# SCH_RFID_FCMS_Pi_Shield_2022-05-20.net
KiCad netlist of a schematic drawn in EasyEDA
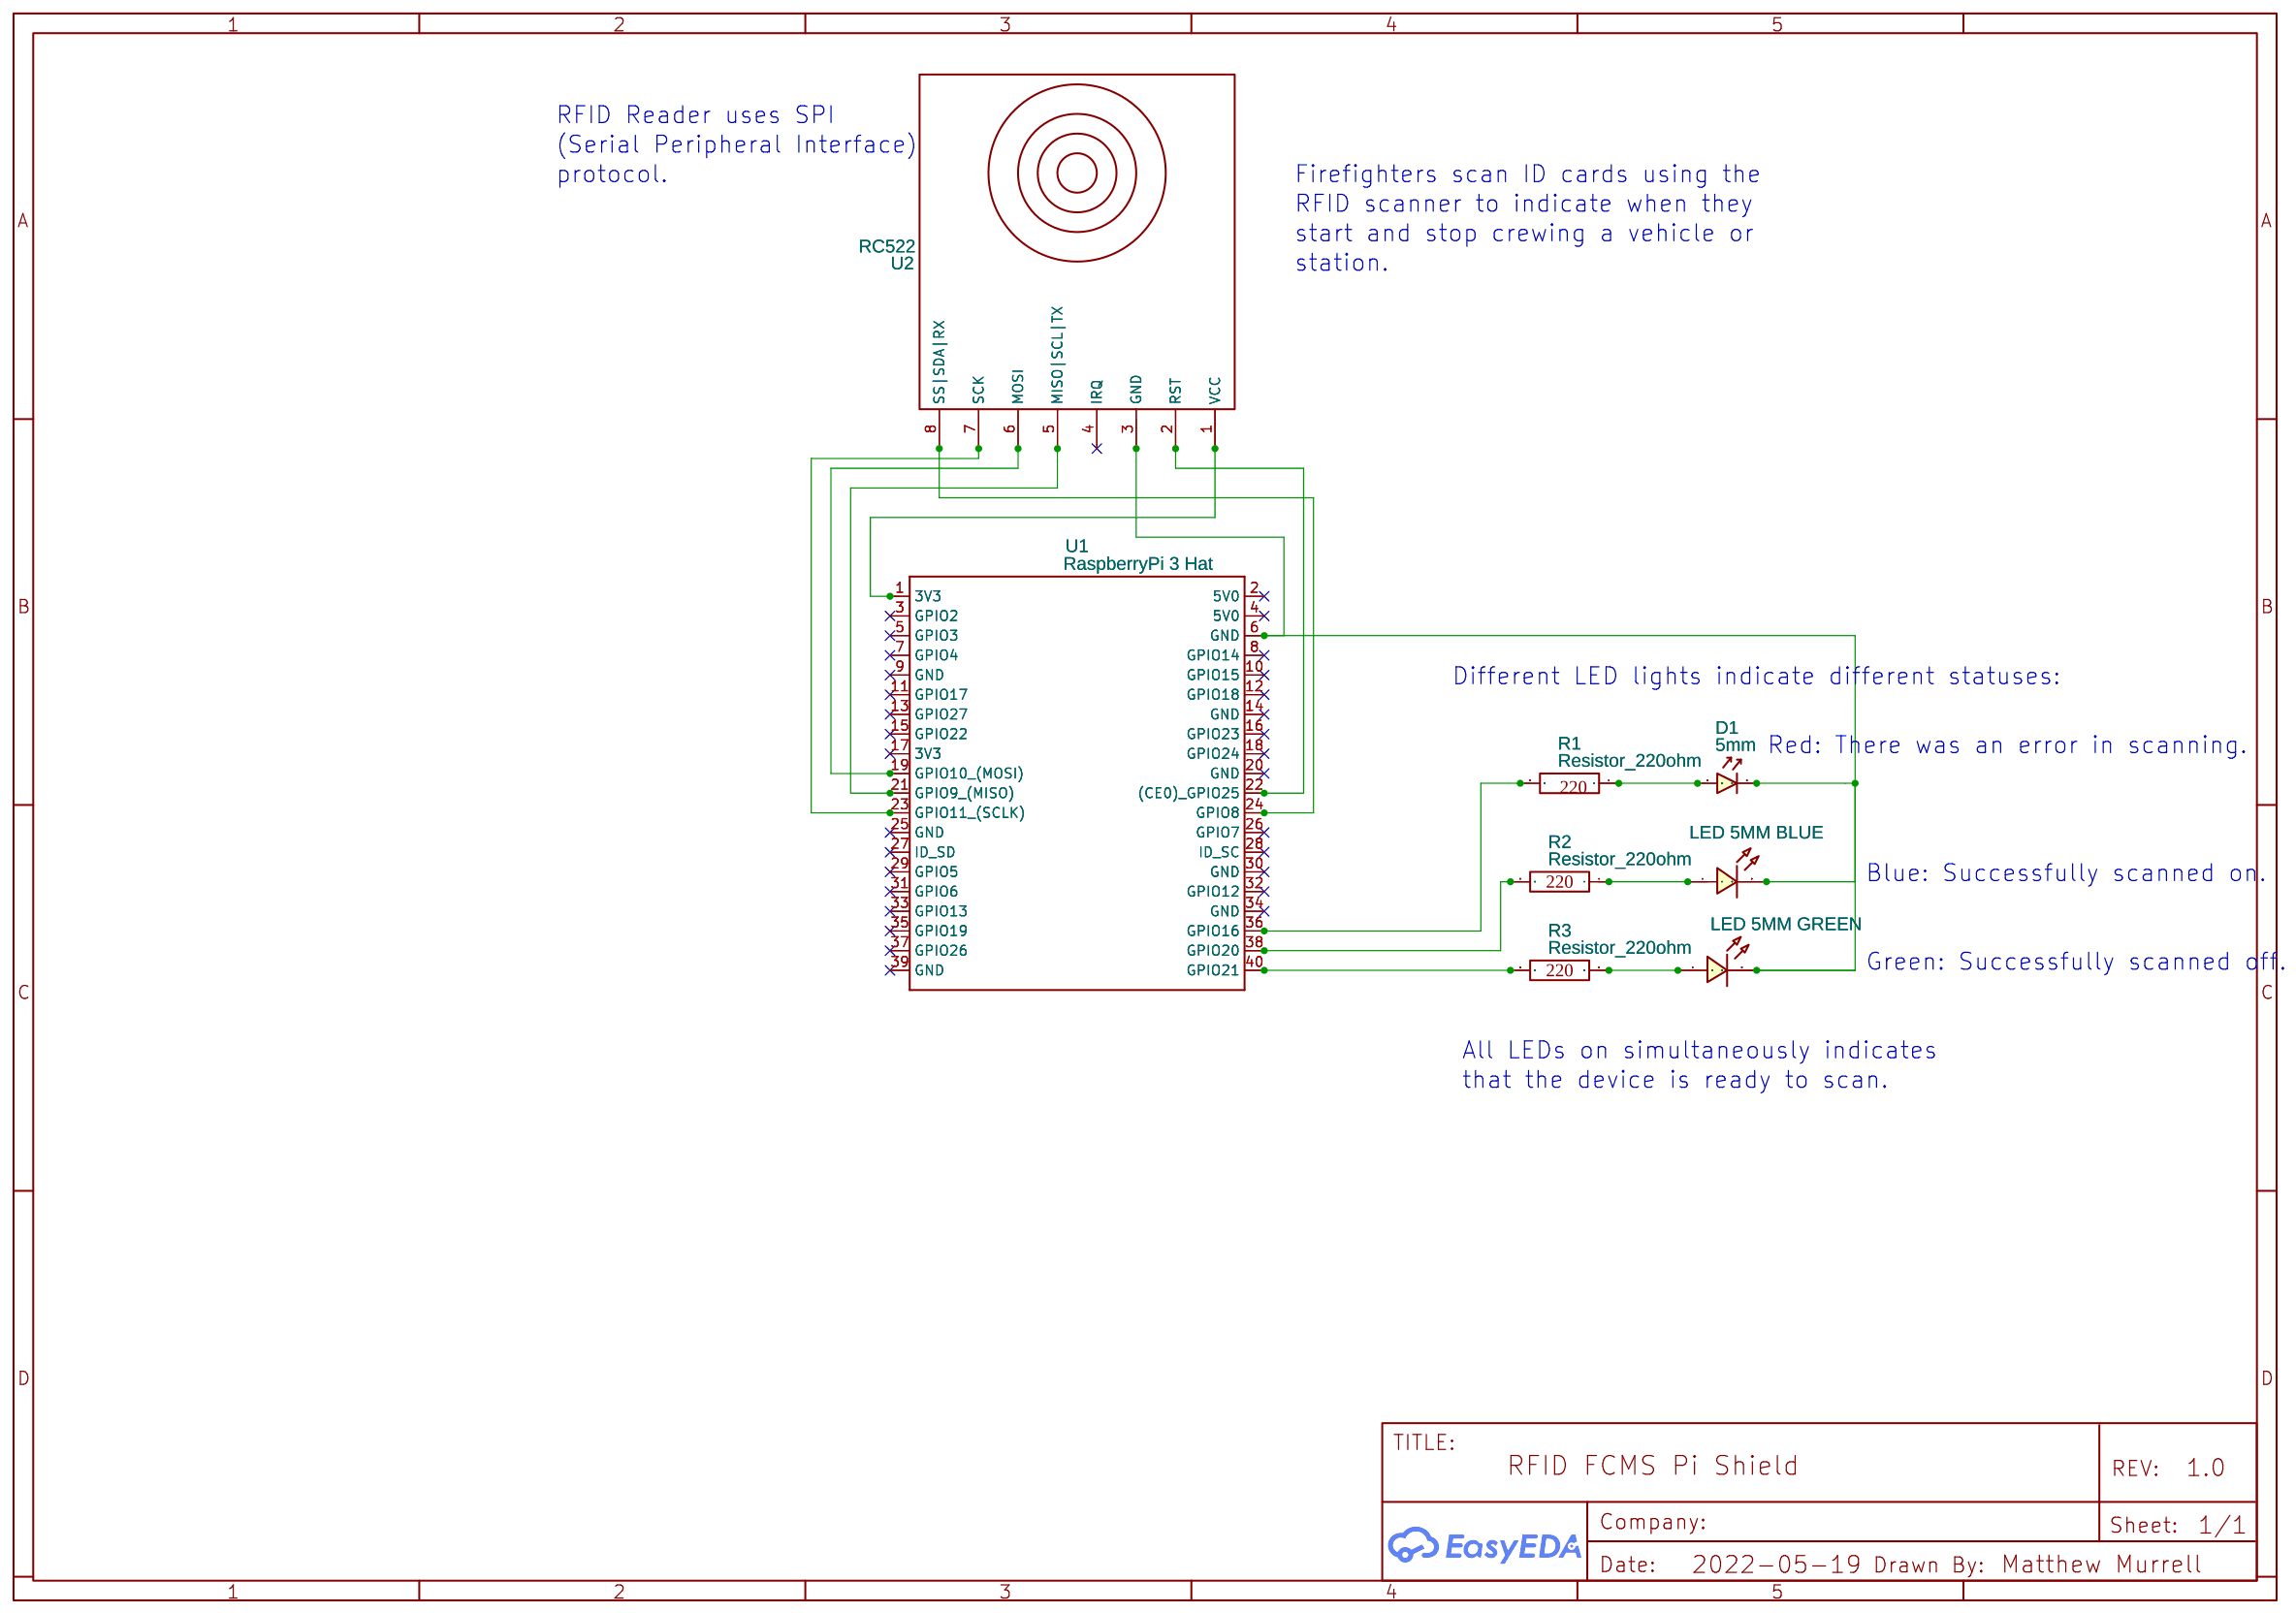
[diagram p0: schematic sheet]

(export (version "E")
  (design (tool "Eeschema 10.0.6"))
  (components
    (comp (ref "1") (value "LED 5MM BLUE") (libsource (lib "") (part "LED 5MM BLUE")))
    (comp (ref "2") (value "LED 5MM GREEN") (libsource (lib "") (part "LED 5MM GREEN")))
    (comp (ref "D1")
      (value "5mm")
      (fields (field (name "BOM_Manufacturer Part") "L-1503EC") (field (name "BOM_Supplier Part") "1003201"))
      (libsource (lib "") (part "L-1503EC"))
    )
    (comp (ref "R1") (value "Resistor_220ohm") (libsource (lib "") (part "Resistor_220ohm_1")))
    (comp (ref "R2") (value "Resistor_220ohm") (libsource (lib "") (part "Resistor_220ohm")))
    (comp (ref "R3") (value "Resistor_220ohm") (libsource (lib "") (part "Resistor_220ohm")))
    (comp (ref "U1")
      (value "RaspberryPi 3 Hat")
      (fields (field (name "BOM_Manufacturer Part") "RaspberryPi 3"))
      (libsource (lib "") (part "RaspberryPi 3 Hat"))
    )
    (comp (ref "U2") (value "RC522") (libsource (lib "") (part "RC522")))
  )
  (nets
    (net (code "1") (name "Net-(1-Pad1)") (class "Default")
      (node (ref "1") (pin "1") (pinfunction "1_1") (pintype "unspecified"))
      (node (ref "R2") (pin "1") (pinfunction "1_1") (pintype "unspecified"))
    )
    (net (code "2") (name "Net-(2-Pad1)") (class "Default")
      (node (ref "2") (pin "1") (pinfunction "1_1") (pintype "unspecified"))
      (node (ref "R3") (pin "1") (pinfunction "1_1") (pintype "unspecified"))
    )
    (net (code "3") (name "Net-(D1-Pad1)") (class "Default")
      (node (ref "D1") (pin "1") (pinfunction "1_1") (pintype "unspecified"))
      (node (ref "R1") (pin "1") (pinfunction "1_1") (pintype "unspecified"))
    )
    (net (code "4") (name "Net-(U1-(CE0)_GPIO25)") (class "Default")
      (node (ref "U1") (pin "22") (pinfunction "(CE0)_GPIO25_22") (pintype "unspecified"))
      (node (ref "U2") (pin "2") (pinfunction "RST_2") (pintype "unspecified"))
    )
    (net (code "5") (name "Net-(U1-GPIO8)") (class "Default")
      (node (ref "U1") (pin "24") (pinfunction "GPIO8_24") (pintype "unspecified"))
      (node (ref "U2") (pin "8") (pinfunction "SS|SDA|RX_8") (pintype "unspecified"))
    )
    (net (code "6") (name "Net-(U1-GPIO9_(MISO))") (class "Default")
      (node (ref "U1") (pin "21") (pinfunction "GPIO9_(MISO)_21") (pintype "unspecified"))
      (node (ref "U2") (pin "5") (pinfunction "MISO|SCL|TX_5") (pintype "unspecified"))
    )
    (net (code "7") (name "Net-(U1-GPIO10_(MOSI))") (class "Default")
      (node (ref "U1") (pin "19") (pinfunction "GPIO10_(MOSI)_19") (pintype "unspecified"))
      (node (ref "U2") (pin "6") (pinfunction "MOSI_6") (pintype "unspecified"))
    )
    (net (code "8") (name "Net-(U1-GPIO11_(SCLK))") (class "Default")
      (node (ref "U1") (pin "23") (pinfunction "GPIO11_(SCLK)_23") (pintype "unspecified"))
      (node (ref "U2") (pin "7") (pinfunction "SCK_7") (pintype "unspecified"))
    )
    (net (code "9") (name "Net-(U1-GPIO16)") (class "Default")
      (node (ref "R1") (pin "2") (pinfunction "2_2") (pintype "unspecified"))
      (node (ref "U1") (pin "36") (pinfunction "GPIO16_36") (pintype "unspecified"))
    )
    (net (code "10") (name "Net-(U1-GPIO20)") (class "Default")
      (node (ref "R2") (pin "2") (pinfunction "2_2") (pintype "unspecified"))
      (node (ref "U1") (pin "38") (pinfunction "GPIO20_38") (pintype "unspecified"))
    )
    (net (code "11") (name "Net-(U1-GPIO21)") (class "Default")
      (node (ref "R3") (pin "2") (pinfunction "2_2") (pintype "unspecified"))
      (node (ref "U1") (pin "40") (pinfunction "GPIO21_40") (pintype "unspecified"))
    )
    (net (code "12") (name "Net-(U2-GND)") (class "Default")
      (node (ref "1") (pin "2") (pinfunction "2_2") (pintype "unspecified"))
      (node (ref "2") (pin "2") (pinfunction "2_2") (pintype "unspecified"))
      (node (ref "D1") (pin "2") (pinfunction "2_2") (pintype "unspecified"))
      (node (ref "U1") (pin "6") (pinfunction "GND_6") (pintype "unspecified"))
      (node (ref "U2") (pin "3") (pinfunction "GND_3") (pintype "unspecified"))
    )
    (net (code "13") (name "Net-(U2-VCC)") (class "Default")
      (node (ref "U1") (pin "1") (pinfunction "3V3_1") (pintype "unspecified"))
      (node (ref "U2") (pin "1") (pinfunction "VCC_1") (pintype "unspecified"))
    )
    (net (code "14") (name "unconnected-(U1-3V3-Pad17)") (class "Default")
      (node (ref "U1") (pin "17") (pinfunction "3V3_17") (pintype "unspecified+no_connect"))
    )
    (net (code "15") (name "unconnected-(U1-5V0-Pad2)") (class "Default")
      (node (ref "U1") (pin "2") (pinfunction "5V0_2") (pintype "unspecified+no_connect"))
    )
    (net (code "16") (name "unconnected-(U1-5V0-Pad4)") (class "Default")
      (node (ref "U1") (pin "4") (pinfunction "5V0_4") (pintype "unspecified+no_connect"))
    )
    (net (code "17") (name "unconnected-(U1-GND-Pad9)") (class "Default")
      (node (ref "U1") (pin "9") (pinfunction "GND_9") (pintype "unspecified+no_connect"))
    )
    (net (code "18") (name "unconnected-(U1-GND-Pad14)") (class "Default")
      (node (ref "U1") (pin "14") (pinfunction "GND_14") (pintype "unspecified+no_connect"))
    )
    (net (code "19") (name "unconnected-(U1-GND-Pad20)") (class "Default")
      (node (ref "U1") (pin "20") (pinfunction "GND_20") (pintype "unspecified+no_connect"))
    )
    (net (code "20") (name "unconnected-(U1-GND-Pad25)") (class "Default")
      (node (ref "U1") (pin "25") (pinfunction "GND_25") (pintype "unspecified+no_connect"))
    )
    (net (code "21") (name "unconnected-(U1-GND-Pad30)") (class "Default")
      (node (ref "U1") (pin "30") (pinfunction "GND_30") (pintype "unspecified+no_connect"))
    )
    (net (code "22") (name "unconnected-(U1-GND-Pad34)") (class "Default")
      (node (ref "U1") (pin "34") (pinfunction "GND_34") (pintype "unspecified+no_connect"))
    )
    (net (code "23") (name "unconnected-(U1-GND-Pad39)") (class "Default")
      (node (ref "U1") (pin "39") (pinfunction "GND_39") (pintype "unspecified+no_connect"))
    )
    (net (code "24") (name "unconnected-(U1-GPIO2-Pad3)") (class "Default")
      (node (ref "U1") (pin "3") (pinfunction "GPIO2_3") (pintype "unspecified+no_connect"))
    )
    (net (code "25") (name "unconnected-(U1-GPIO3-Pad5)") (class "Default")
      (node (ref "U1") (pin "5") (pinfunction "GPIO3_5") (pintype "unspecified+no_connect"))
    )
    (net (code "26") (name "unconnected-(U1-GPIO4-Pad7)") (class "Default")
      (node (ref "U1") (pin "7") (pinfunction "GPIO4_7") (pintype "unspecified+no_connect"))
    )
    (net (code "27") (name "unconnected-(U1-GPIO5-Pad29)") (class "Default")
      (node (ref "U1") (pin "29") (pinfunction "GPIO5_29") (pintype "unspecified+no_connect"))
    )
    (net (code "28") (name "unconnected-(U1-GPIO6-Pad31)") (class "Default")
      (node (ref "U1") (pin "31") (pinfunction "GPIO6_31") (pintype "unspecified+no_connect"))
    )
    (net (code "29") (name "unconnected-(U1-GPIO7-Pad26)") (class "Default")
      (node (ref "U1") (pin "26") (pinfunction "GPIO7_26") (pintype "unspecified+no_connect"))
    )
    (net (code "30") (name "unconnected-(U1-GPIO12-Pad32)") (class "Default")
      (node (ref "U1") (pin "32") (pinfunction "GPIO12_32") (pintype "unspecified+no_connect"))
    )
    (net (code "31") (name "unconnected-(U1-GPIO13-Pad33)") (class "Default")
      (node (ref "U1") (pin "33") (pinfunction "GPIO13_33") (pintype "unspecified+no_connect"))
    )
    (net (code "32") (name "unconnected-(U1-GPIO14-Pad8)") (class "Default")
      (node (ref "U1") (pin "8") (pinfunction "GPIO14_8") (pintype "unspecified+no_connect"))
    )
    (net (code "33") (name "unconnected-(U1-GPIO15-Pad10)") (class "Default")
      (node (ref "U1") (pin "10") (pinfunction "GPIO15_10") (pintype "unspecified+no_connect"))
    )
    (net (code "34") (name "unconnected-(U1-GPIO17-Pad11)") (class "Default")
      (node (ref "U1") (pin "11") (pinfunction "GPIO17_11") (pintype "unspecified+no_connect"))
    )
    (net (code "35") (name "unconnected-(U1-GPIO18-Pad12)") (class "Default")
      (node (ref "U1") (pin "12") (pinfunction "GPIO18_12") (pintype "unspecified+no_connect"))
    )
    (net (code "36") (name "unconnected-(U1-GPIO19-Pad35)") (class "Default")
      (node (ref "U1") (pin "35") (pinfunction "GPIO19_35") (pintype "unspecified+no_connect"))
    )
    (net (code "37") (name "unconnected-(U1-GPIO22-Pad15)") (class "Default")
      (node (ref "U1") (pin "15") (pinfunction "GPIO22_15") (pintype "unspecified+no_connect"))
    )
    (net (code "38") (name "unconnected-(U1-GPIO23-Pad16)") (class "Default")
      (node (ref "U1") (pin "16") (pinfunction "GPIO23_16") (pintype "unspecified+no_connect"))
    )
    (net (code "39") (name "unconnected-(U1-GPIO24-Pad18)") (class "Default")
      (node (ref "U1") (pin "18") (pinfunction "GPIO24_18") (pintype "unspecified+no_connect"))
    )
    (net (code "40") (name "unconnected-(U1-GPIO26-Pad37)") (class "Default")
      (node (ref "U1") (pin "37") (pinfunction "GPIO26_37") (pintype "unspecified+no_connect"))
    )
    (net (code "41") (name "unconnected-(U1-GPIO27-Pad13)") (class "Default")
      (node (ref "U1") (pin "13") (pinfunction "GPIO27_13") (pintype "unspecified+no_connect"))
    )
    (net (code "42") (name "unconnected-(U1-ID_SC-Pad28)") (class "Default")
      (node (ref "U1") (pin "28") (pinfunction "ID_SC_28") (pintype "unspecified+no_connect"))
    )
    (net (code "43") (name "unconnected-(U1-ID_SD-Pad27)") (class "Default")
      (node (ref "U1") (pin "27") (pinfunction "ID_SD_27") (pintype "unspecified+no_connect"))
    )
    (net (code "44") (name "unconnected-(U2-IRQ-Pad4)") (class "Default")
      (node (ref "U2") (pin "4") (pinfunction "IRQ_4") (pintype "unspecified+no_connect"))
    )
  )
)
